# doodle_8_with_step_and_l293.net
KiCad netlist of a schematic drawn in EAGLE
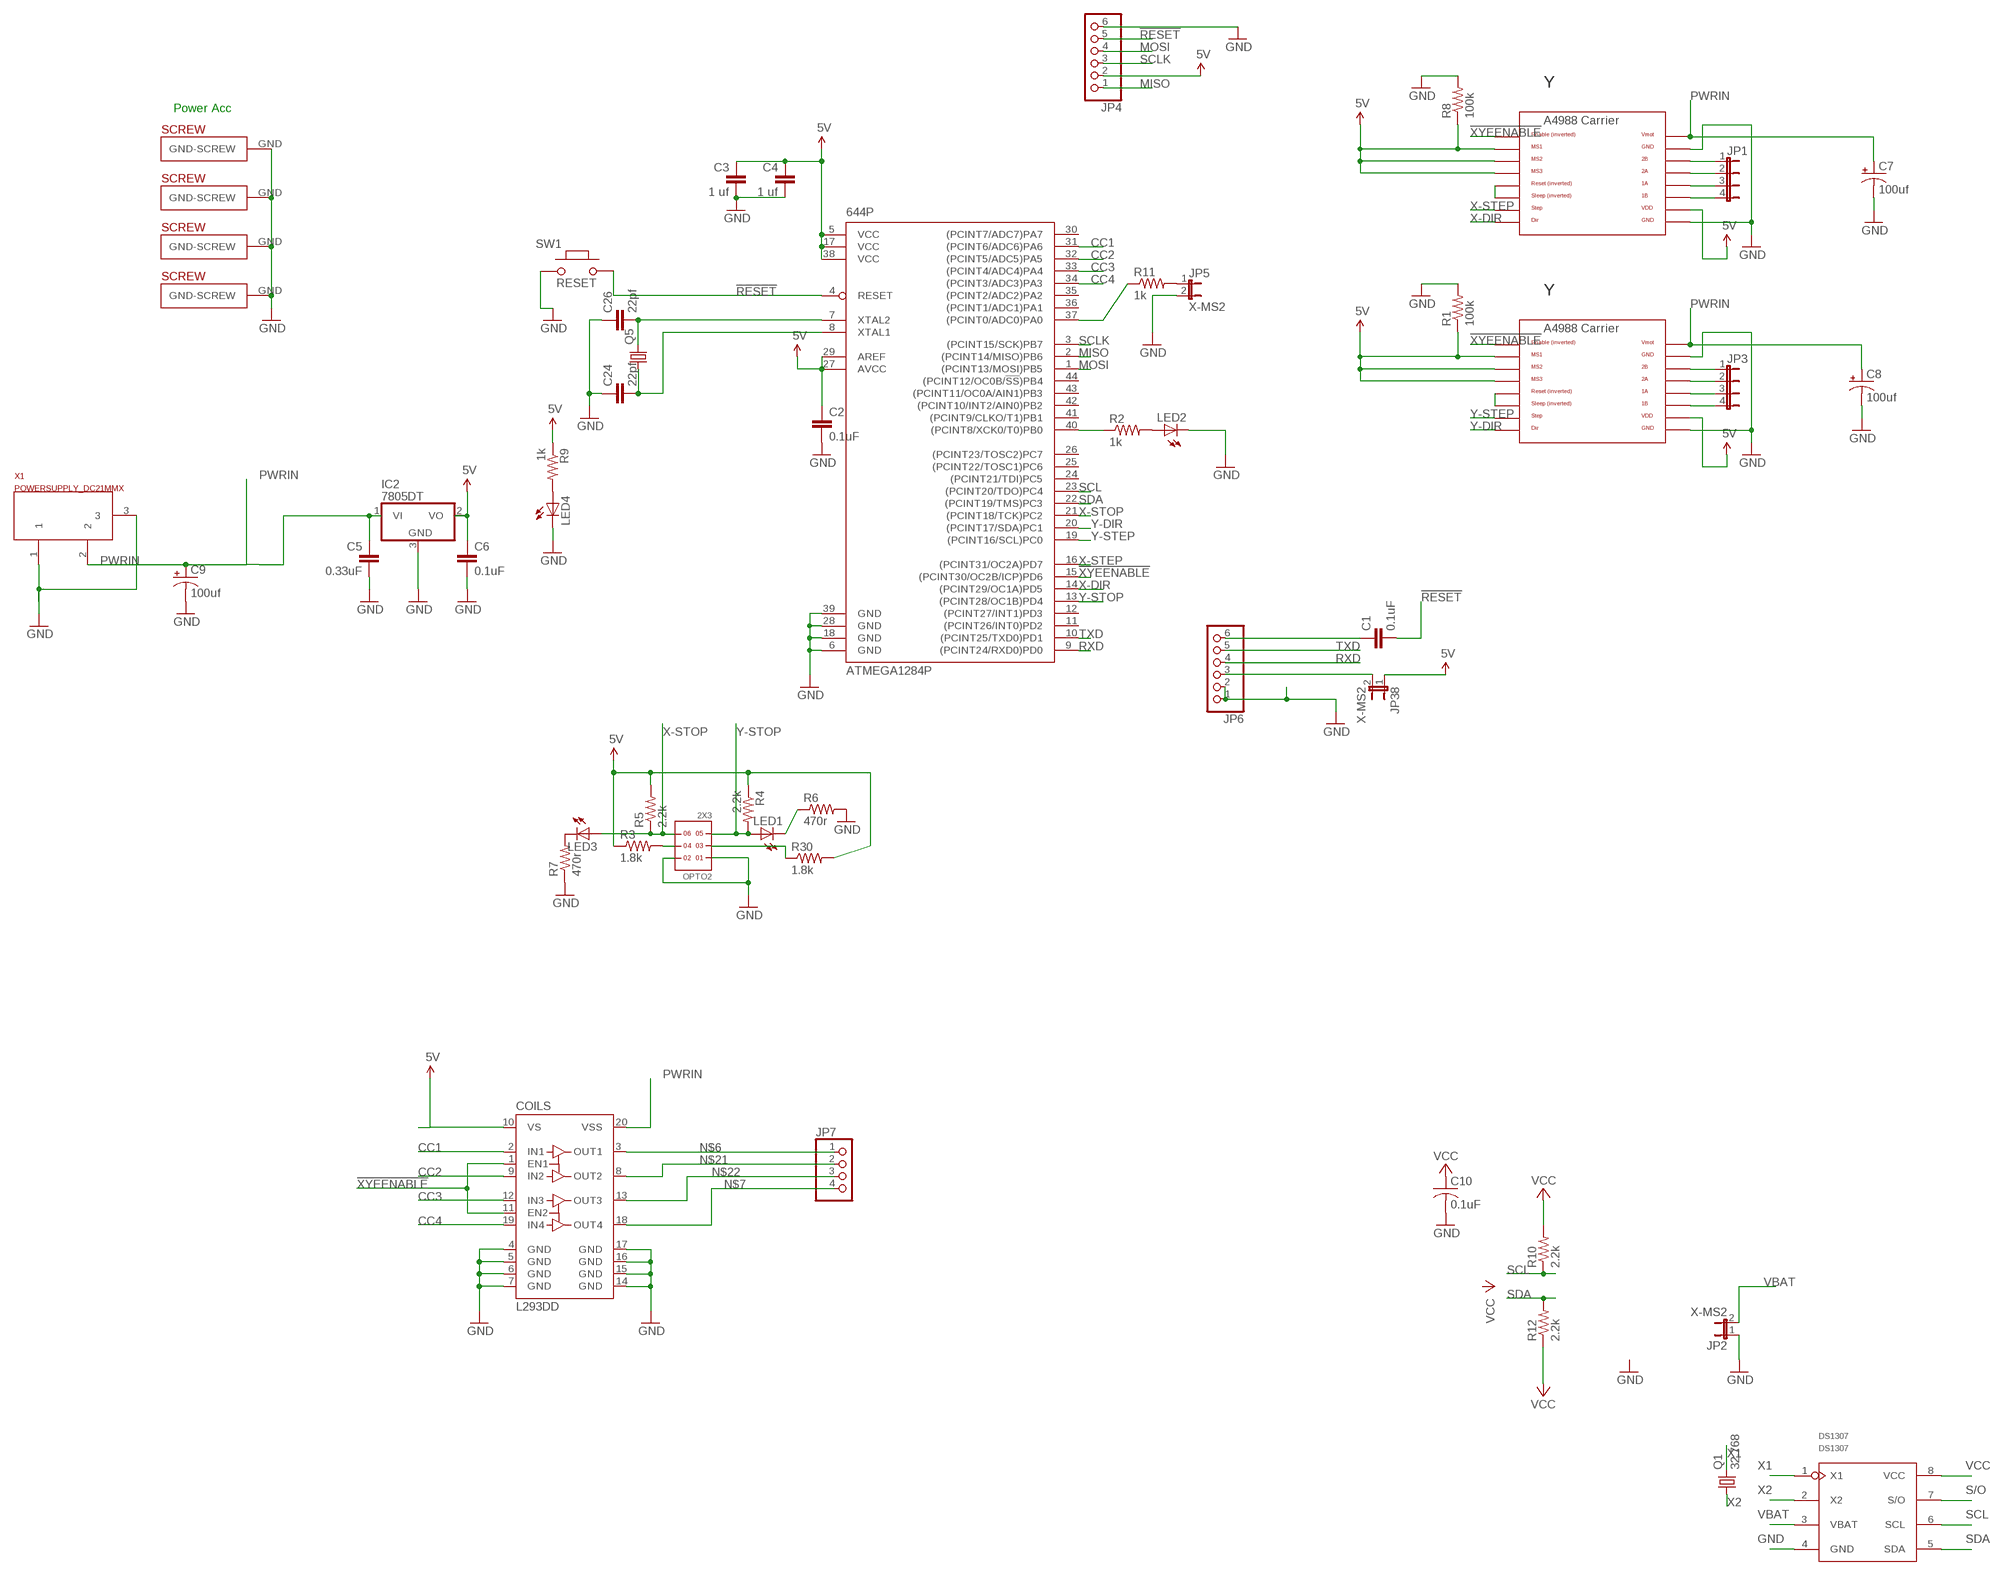
[diagram p0: schematic, sheet 1]

(export (version "E")
  (design (tool "Eeschema 10.0.6"))
  (components
    (comp (ref "644P")
      (value "ATMEGA1284P")
      (footprint "eagle-import:TQFP44")
      (fields (field (name "MPN") "ATMEGA644PV-10AU"))
      (libsource (lib "eagle-import") (part "ATMEGA644A"))
    )
    (comp (ref "C1")
      (value "0.1uF")
      (footprint "eagle-import:0805")
      (libsource (lib "eagle-import") (part "CAP0805"))
    )
    (comp (ref "C2")
      (value "0.1uF")
      (footprint "eagle-import:0805")
      (libsource (lib "eagle-import") (part "CAP0805"))
    )
    (comp (ref "C3")
      (value "1 uf")
      (footprint "eagle-import:0805")
      (libsource (lib "eagle-import") (part "CAP0805"))
    )
    (comp (ref "C4")
      (value "1 uf")
      (footprint "eagle-import:0805")
      (libsource (lib "eagle-import") (part "CAP0805"))
    )
    (comp (ref "C5")
      (value "0.33uF")
      (footprint "eagle-import:CAP-PTH-SMALL2")
      (libsource (lib "eagle-import") (part "CAPPTH2"))
    )
    (comp (ref "C6")
      (value "0.1uF")
      (footprint "eagle-import:CAP-PTH-SMALL2")
      (libsource (lib "eagle-import") (part "CAPPTH2"))
    )
    (comp (ref "C7")
      (value "100uf")
      (footprint "eagle-import:CPOL-RADIAL-100UF-25V")
      (libsource (lib "eagle-import") (part "CAP_POLPTH1"))
    )
    (comp (ref "C8")
      (value "100uf")
      (footprint "eagle-import:CPOL-RADIAL-100UF-25V")
      (libsource (lib "eagle-import") (part "CAP_POLPTH1"))
    )
    (comp (ref "C9")
      (value "100uf")
      (footprint "eagle-import:CPOL-RADIAL-100UF-25V")
      (libsource (lib "eagle-import") (part "CAP_POLPTH1"))
    )
    (comp (ref "C10")
      (value "0.1uF")
      (footprint "eagle-import:C0805")
      (libsource (lib "eagle-import") (part "C-USC0805"))
    )
    (comp (ref "C24")
      (value "22pf")
      (footprint "eagle-import:0805")
      (libsource (lib "eagle-import") (part "CAP0805"))
    )
    (comp (ref "C26")
      (value "22pf")
      (footprint "eagle-import:0805")
      (libsource (lib "eagle-import") (part "CAP0805"))
    )
    (comp (ref "COILS")
      (value "L293DD")
      (footprint "eagle-import:SO20")
      (libsource (lib "eagle-import") (part "L293DD"))
    )
    (comp (ref "DS1307")
      (value "DS1307")
      (footprint "eagle-import:SO08")
      (libsource (lib "eagle-import") (part "DS1307"))
    )
    (comp (ref "IC2")
      (value "7805DT")
      (footprint "eagle-import:TO252")
      (libsource (lib "eagle-import") (part "78DT05"))
    )
    (comp (ref "JP1")
      (value "JP4E")
      (footprint "eagle-import:JP4")
      (libsource (lib "eagle-import") (part "JP4E"))
    )
    (comp (ref "JP2")
      (value "X-MS2")
      (footprint "eagle-import:1X02")
      (libsource (lib "eagle-import") (part "JUMPER-2PTH"))
    )
    (comp (ref "JP3")
      (value "JP4E")
      (footprint "eagle-import:JP4")
      (libsource (lib "eagle-import") (part "JP4E"))
    )
    (comp (ref "JP4")
      (value "PINHD-1X6/90")
      (footprint "eagle-import:1X06_90")
      (libsource (lib "eagle-import") (part "PINHD-1X6/90"))
    )
    (comp (ref "JP5")
      (value "X-MS2")
      (footprint "eagle-import:1X02")
      (libsource (lib "eagle-import") (part "JUMPER-2PTH"))
    )
    (comp (ref "JP6")
      (value "PINHD-1X6")
      (footprint "eagle-import:1X06")
      (libsource (lib "eagle-import") (part "PINHD-1X6"))
    )
    (comp (ref "JP7")
      (value "PINHD-1X04_2.54")
      (footprint "eagle-import:1X04")
      (libsource (lib "eagle-import") (part "PINHD-1X04_2.54"))
    )
    (comp (ref "JP38")
      (value "X-MS2")
      (footprint "eagle-import:1X02")
      (libsource (lib "eagle-import") (part "JUMPER-2PTH"))
    )
    (comp (ref "LED1")
      (value "LEDCHIPLED_0805")
      (footprint "eagle-import:CHIPLED_0805")
      (libsource (lib "eagle-import") (part "LEDCHIPLED_0805"))
    )
    (comp (ref "LED2")
      (value "LEDCHIPLED_0805")
      (footprint "eagle-import:CHIPLED_0805")
      (libsource (lib "eagle-import") (part "LEDCHIPLED_0805"))
    )
    (comp (ref "LED3")
      (value "LEDCHIPLED_0805")
      (footprint "eagle-import:CHIPLED_0805")
      (libsource (lib "eagle-import") (part "LEDCHIPLED_0805"))
    )
    (comp (ref "LED4")
      (value "LEDCHIPLED_0805")
      (footprint "eagle-import:CHIPLED_0805")
      (libsource (lib "eagle-import") (part "LEDCHIPLED_0805"))
    )
    (comp (ref "OPTO2")
      (value "2X3")
      (footprint "eagle-import:2X3")
      (libsource (lib "eagle-import") (part "2X3"))
    )
    (comp (ref "Q1")
      (value "32.768")
      (footprint "eagle-import:TC38H")
      (libsource (lib "eagle-import") (part "CRYTALTC38H"))
    )
    (comp (ref "Q5")
      (value "CRYSTALHC49S")
      (footprint "eagle-import:HC49_S")
      (libsource (lib "eagle-import") (part "CRYSTALHC49S"))
    )
    (comp (ref "R1")
      (value "100k")
      (footprint "eagle-import:R0805")
      (libsource (lib "eagle-import") (part "R-US_R0805"))
    )
    (comp (ref "R2")
      (value "1k")
      (footprint "eagle-import:R0805")
      (libsource (lib "eagle-import") (part "R-US_R0805"))
    )
    (comp (ref "R3")
      (value "1.8k")
      (footprint "eagle-import:R0805")
      (libsource (lib "eagle-import") (part "R-US_R0805"))
    )
    (comp (ref "R4")
      (value "2.2k")
      (footprint "eagle-import:R0805")
      (libsource (lib "eagle-import") (part "R-US_R0805"))
    )
    (comp (ref "R5")
      (value "2.2k")
      (footprint "eagle-import:R0805")
      (libsource (lib "eagle-import") (part "R-US_R0805"))
    )
    (comp (ref "R6")
      (value "470r")
      (footprint "eagle-import:R0805")
      (libsource (lib "eagle-import") (part "R-US_R0805"))
    )
    (comp (ref "R7")
      (value "470r")
      (footprint "eagle-import:R0805")
      (libsource (lib "eagle-import") (part "R-US_R0805"))
    )
    (comp (ref "R8")
      (value "100k")
      (footprint "eagle-import:R0805")
      (libsource (lib "eagle-import") (part "R-US_R0805"))
    )
    (comp (ref "R9")
      (value "1k")
      (footprint "eagle-import:R0805")
      (libsource (lib "eagle-import") (part "R-US_R0805"))
    )
    (comp (ref "R10")
      (value "2.2k")
      (footprint "eagle-import:R0805")
      (libsource (lib "eagle-import") (part "R-US_R0805"))
    )
    (comp (ref "R11")
      (value "1k")
      (footprint "eagle-import:R0805")
      (libsource (lib "eagle-import") (part "R-US_R0805"))
    )
    (comp (ref "R12")
      (value "2.2k")
      (footprint "eagle-import:R0805")
      (libsource (lib "eagle-import") (part "R-US_R0805"))
    )
    (comp (ref "R30")
      (value "1.8k")
      (footprint "eagle-import:R0603")
      (libsource (lib "eagle-import") (part "R-US_R0603"))
    )
    (comp (ref "SW1")
      (value "RESET")
      (footprint "eagle-import:157SW")
      (libsource (lib "eagle-import") (part "PB157"))
    )
    (comp (ref "U$1")
      (value "A4988BREAKOUT")
      (footprint "eagle-import:A4988BREAKOUT")
      (libsource (lib "eagle-import") (part "A4988BREAKOUT"))
    )
    (comp (ref "U$7")
      (value "A4988BREAKOUT")
      (footprint "eagle-import:A4988BREAKOUT")
      (libsource (lib "eagle-import") (part "A4988BREAKOUT"))
    )
    (comp (ref "U$14")
      (value "PLATED-SCREW")
      (footprint "eagle-import:PLATEDSCREW")
      (libsource (lib "eagle-import") (part "PLATED-SCREW"))
    )
    (comp (ref "U$17")
      (value "PLATED-SCREW")
      (footprint "eagle-import:PLATEDSCREW")
      (libsource (lib "eagle-import") (part "PLATED-SCREW"))
    )
    (comp (ref "U$18")
      (value "PLATED-SCREW")
      (footprint "eagle-import:PLATEDSCREW")
      (libsource (lib "eagle-import") (part "PLATED-SCREW"))
    )
    (comp (ref "U$38")
      (value "PLATED-SCREW")
      (footprint "eagle-import:PLATEDSCREW")
      (libsource (lib "eagle-import") (part "PLATED-SCREW"))
    )
    (comp (ref "X1")
      (value "POWERSUPPLY_DC21MMX")
      (footprint "eagle-import:POWERSUPPLY_DC-21MM")
      (libsource (lib "eagle-import") (part "POWERSUPPLY_DC21MMX"))
    )
  )
  (nets
    (net (code "1") (name "/CC1") (class "Default")
      (node (ref "644P") (pin "31") (pinfunction "(PCINT6/ADC6)PA6_31") (pintype "bidirectional"))
      (node (ref "COILS") (pin "2") (pinfunction "IN1_2") (pintype "input"))
    )
    (net (code "2") (name "/CC2") (class "Default")
      (node (ref "644P") (pin "32") (pinfunction "(PCINT5/ADC5)PA5_32") (pintype "bidirectional"))
      (node (ref "COILS") (pin "9") (pinfunction "IN2_9") (pintype "input"))
    )
    (net (code "3") (name "/CC3") (class "Default")
      (node (ref "644P") (pin "33") (pinfunction "(PCINT4/ADC4)PA4_33") (pintype "bidirectional"))
      (node (ref "COILS") (pin "12") (pinfunction "IN3_12") (pintype "input"))
    )
    (net (code "4") (name "/CC4") (class "Default")
      (node (ref "644P") (pin "34") (pinfunction "(PCINT3/ADC3)PA3_34") (pintype "bidirectional"))
      (node (ref "COILS") (pin "19") (pinfunction "IN4_19") (pintype "input"))
    )
    (net (code "5") (name "/MISO") (class "Default")
      (node (ref "644P") (pin "2") (pinfunction "(PCINT14/MISO)PB6_2") (pintype "bidirectional"))
      (node (ref "JP4") (pin "1") (pinfunction "1_1") (pintype "passive"))
    )
    (net (code "6") (name "/MOSI") (class "Default")
      (node (ref "644P") (pin "1") (pinfunction "(PCINT13/MOSI)PB5_1") (pintype "bidirectional"))
      (node (ref "JP4") (pin "4") (pinfunction "4_4") (pintype "passive"))
    )
    (net (code "7") (name "/N$6") (class "Default")
      (node (ref "COILS") (pin "3") (pinfunction "OUT1_3") (pintype "output"))
      (node (ref "JP7") (pin "1") (pinfunction "1_1") (pintype "passive"))
    )
    (net (code "8") (name "/N$7") (class "Default")
      (node (ref "COILS") (pin "18") (pinfunction "OUT4_18") (pintype "output"))
      (node (ref "JP7") (pin "4") (pinfunction "4_4") (pintype "passive"))
    )
    (net (code "9") (name "/N$21") (class "Default")
      (node (ref "COILS") (pin "8") (pinfunction "OUT2_8") (pintype "output"))
      (node (ref "JP7") (pin "2") (pinfunction "2_2") (pintype "passive"))
    )
    (net (code "10") (name "/N$22") (class "Default")
      (node (ref "COILS") (pin "13") (pinfunction "OUT3_13") (pintype "output"))
      (node (ref "JP7") (pin "3") (pinfunction "3_3") (pintype "passive"))
    )
    (net (code "11") (name "/PWRIN") (class "Default")
      (node (ref "C5") (pin "1") (pinfunction "1_1") (pintype "passive"))
      (node (ref "C7") (pin "1") (pinfunction "+_1") (pintype "passive"))
      (node (ref "C8") (pin "1") (pinfunction "+_1") (pintype "passive"))
      (node (ref "C9") (pin "1") (pinfunction "+_1") (pintype "passive"))
      (node (ref "COILS") (pin "20") (pinfunction "VSS_20") (pintype "power_in"))
      (node (ref "IC2") (pin "1") (pinfunction "VI_1") (pintype "input"))
      (node (ref "U$1") (pin "VMOT") (pinfunction "VMOT_VMOT") (pintype "power_in"))
      (node (ref "U$7") (pin "VMOT") (pinfunction "VMOT_VMOT") (pintype "power_in"))
      (node (ref "X1") (pin "2") (pinfunction "2_2") (pintype "power_in"))
    )
    (net (code "12") (name "/RXD") (class "Default")
      (node (ref "644P") (pin "9") (pinfunction "(PCINT24/RXD0)PD0_9") (pintype "bidirectional"))
      (node (ref "JP6") (pin "4") (pinfunction "4_4") (pintype "passive"))
    )
    (net (code "13") (name "/SCL") (class "Default")
      (node (ref "644P") (pin "23") (pinfunction "(PCINT20/TDO)PC4_23") (pintype "output"))
      (node (ref "DS1307") (pin "6") (pinfunction "SCL_6") (pintype "bidirectional"))
      (node (ref "R10") (pin "1") (pinfunction "1_1") (pintype "passive"))
    )
    (net (code "14") (name "/SCLK") (class "Default")
      (node (ref "644P") (pin "3") (pinfunction "(PCINT15/SCK)PB7_3") (pintype "bidirectional"))
      (node (ref "JP4") (pin "3") (pinfunction "3_3") (pintype "passive"))
    )
    (net (code "15") (name "/SDA") (class "Default")
      (node (ref "644P") (pin "22") (pinfunction "(PCINT19/TMS)PC3_22") (pintype "output"))
      (node (ref "DS1307") (pin "5") (pinfunction "SDA_5") (pintype "bidirectional"))
      (node (ref "R12") (pin "2") (pinfunction "2_2") (pintype "passive"))
    )
    (net (code "16") (name "/S{slash}O") (class "Default")
      (node (ref "DS1307") (pin "7") (pinfunction "S/O_7") (pintype "bidirectional"))
    )
    (net (code "17") (name "/TXD") (class "Default")
      (node (ref "644P") (pin "10") (pinfunction "(PCINT25/TXD0)PD1_10") (pintype "bidirectional"))
      (node (ref "JP6") (pin "5") (pinfunction "5_5") (pintype "passive"))
    )
    (net (code "18") (name "/VBAT") (class "Default")
      (node (ref "DS1307") (pin "3") (pinfunction "VBAT_3") (pintype "bidirectional"))
      (node (ref "JP2") (pin "2") (pinfunction "2_2") (pintype "passive"))
    )
    (net (code "19") (name "/X-DIR") (class "Default")
      (node (ref "644P") (pin "14") (pinfunction "(PCINT29/OC1A)PD5_14") (pintype "bidirectional"))
      (node (ref "U$7") (pin "DIR") (pinfunction "DIR_DIR") (pintype "input"))
    )
    (net (code "20") (name "/X-STEP") (class "Default")
      (node (ref "644P") (pin "16") (pinfunction "(PCINT31/OC2A)PD7_16") (pintype "bidirectional"))
      (node (ref "U$7") (pin "STEP") (pinfunction "STEP_STEP") (pintype "input"))
    )
    (net (code "21") (name "/X-STOP") (class "Default")
      (node (ref "644P") (pin "21") (pinfunction "(PCINT18/TCK)PC2_21") (pintype "output"))
      (node (ref "LED3") (pin "A") (pinfunction "A_A") (pintype "passive"))
      (node (ref "OPTO2") (pin "6") (pinfunction "6_6") (pintype "bidirectional"))
      (node (ref "R5") (pin "1") (pinfunction "1_1") (pintype "passive"))
    )
    (net (code "22") (name "/X1") (class "Default")
      (node (ref "DS1307") (pin "1") (pinfunction "X1_1") (pintype "bidirectional"))
      (node (ref "Q1") (pin "2") (pinfunction "2_2") (pintype "passive"))
    )
    (net (code "23") (name "/X2") (class "Default")
      (node (ref "DS1307") (pin "2") (pinfunction "X2_2") (pintype "bidirectional"))
      (node (ref "Q1") (pin "1") (pinfunction "1_1") (pintype "passive"))
    )
    (net (code "24") (name "/Y-DIR") (class "Default")
      (node (ref "644P") (pin "20") (pinfunction "(PCINT17/SDA)PC1_20") (pintype "output"))
      (node (ref "U$1") (pin "DIR") (pinfunction "DIR_DIR") (pintype "input"))
    )
    (net (code "25") (name "/Y-STEP") (class "Default")
      (node (ref "644P") (pin "19") (pinfunction "(PCINT16/SCL)PC0_19") (pintype "output"))
      (node (ref "U$1") (pin "STEP") (pinfunction "STEP_STEP") (pintype "input"))
    )
    (net (code "26") (name "/Y-STOP") (class "Default")
      (node (ref "644P") (pin "13") (pinfunction "(PCINT28/OC1B)PD4_13") (pintype "bidirectional"))
      (node (ref "LED1") (pin "A") (pinfunction "A_A") (pintype "passive"))
      (node (ref "OPTO2") (pin "5") (pinfunction "5_5") (pintype "bidirectional"))
      (node (ref "R4") (pin "2") (pinfunction "2_2") (pintype "passive"))
    )
    (net (code "27") (name "/~{RESET}") (class "Default")
      (node (ref "644P") (pin "4") (pinfunction "RESET_4") (pintype "input"))
      (node (ref "C1") (pin "2") (pinfunction "2_2") (pintype "passive"))
      (node (ref "JP4") (pin "5") (pinfunction "5_5") (pintype "passive"))
      (node (ref "SW1") (pin "2") (pinfunction "2_2") (pintype "passive"))
    )
    (net (code "28") (name "/~{XYEENABLE}") (class "Default")
      (node (ref "644P") (pin "15") (pinfunction "(PCINT30/OC2B/ICP)PD6_15") (pintype "bidirectional"))
      (node (ref "COILS") (pin "1") (pinfunction "EN1_1") (pintype "input"))
      (node (ref "COILS") (pin "11") (pinfunction "EN2_11") (pintype "input"))
      (node (ref "U$1") (pin "EN") (pinfunction "EN_EN") (pintype "input"))
      (node (ref "U$7") (pin "EN") (pinfunction "EN_EN") (pintype "input"))
    )
    (net (code "29") (name "5V") (class "Default")
      (node (ref "644P") (pin "17") (pinfunction "VCC_17") (pintype "power_in"))
      (node (ref "644P") (pin "27") (pinfunction "AVCC_27") (pintype "power_in"))
      (node (ref "644P") (pin "29") (pinfunction "AREF_29") (pintype "passive"))
      (node (ref "644P") (pin "38") (pinfunction "VCC_38") (pintype "power_in"))
      (node (ref "644P") (pin "5") (pinfunction "VCC_5") (pintype "power_in"))
      (node (ref "C2") (pin "1") (pinfunction "1_1") (pintype "passive"))
      (node (ref "C3") (pin "1") (pinfunction "1_1") (pintype "passive"))
      (node (ref "C4") (pin "1") (pinfunction "1_1") (pintype "passive"))
      (node (ref "C6") (pin "1") (pinfunction "1_1") (pintype "passive"))
      (node (ref "COILS") (pin "10") (pinfunction "VS_10") (pintype "power_in"))
      (node (ref "IC2") (pin "2") (pinfunction "VO_2") (pintype "passive"))
      (node (ref "JP38") (pin "1") (pinfunction "1_1") (pintype "passive"))
      (node (ref "JP4") (pin "2") (pinfunction "2_2") (pintype "passive"))
      (node (ref "R1") (pin "1") (pinfunction "1_1") (pintype "passive"))
      (node (ref "R3") (pin "1") (pinfunction "1_1") (pintype "passive"))
      (node (ref "R30") (pin "2") (pinfunction "2_2") (pintype "passive"))
      (node (ref "R4") (pin "1") (pinfunction "1_1") (pintype "passive"))
      (node (ref "R5") (pin "2") (pinfunction "2_2") (pintype "passive"))
      (node (ref "R8") (pin "1") (pinfunction "1_1") (pintype "passive"))
      (node (ref "R9") (pin "1") (pinfunction "1_1") (pintype "passive"))
      (node (ref "U$1") (pin "MS1") (pinfunction "MS1_MS1") (pintype "input"))
      (node (ref "U$1") (pin "MS2") (pinfunction "MS2_MS2") (pintype "input"))
      (node (ref "U$1") (pin "MS3") (pinfunction "MS3_MS3") (pintype "input"))
      (node (ref "U$1") (pin "VDD") (pinfunction "VDD_VDD") (pintype "power_in"))
      (node (ref "U$7") (pin "MS1") (pinfunction "MS1_MS1") (pintype "input"))
      (node (ref "U$7") (pin "MS2") (pinfunction "MS2_MS2") (pintype "input"))
      (node (ref "U$7") (pin "MS3") (pinfunction "MS3_MS3") (pintype "input"))
      (node (ref "U$7") (pin "VDD") (pinfunction "VDD_VDD") (pintype "power_in"))
    )
    (net (code "30") (name "GND") (class "Default")
      (node (ref "644P") (pin "18") (pinfunction "GND_18") (pintype "power_in"))
      (node (ref "644P") (pin "28") (pinfunction "GND_28") (pintype "power_in"))
      (node (ref "644P") (pin "39") (pinfunction "GND_39") (pintype "power_in"))
      (node (ref "644P") (pin "6") (pinfunction "GND_6") (pintype "power_in"))
      (node (ref "C10") (pin "2") (pinfunction "2_2") (pintype "passive"))
      (node (ref "C2") (pin "2") (pinfunction "2_2") (pintype "passive"))
      (node (ref "C24") (pin "1") (pinfunction "1_1") (pintype "passive"))
      (node (ref "C26") (pin "1") (pinfunction "1_1") (pintype "passive"))
      (node (ref "C3") (pin "2") (pinfunction "2_2") (pintype "passive"))
      (node (ref "C4") (pin "2") (pinfunction "2_2") (pintype "passive"))
      (node (ref "C5") (pin "2") (pinfunction "2_2") (pintype "passive"))
      (node (ref "C6") (pin "2") (pinfunction "2_2") (pintype "passive"))
      (node (ref "C7") (pin "2") (pinfunction "-_2") (pintype "passive"))
      (node (ref "C8") (pin "2") (pinfunction "-_2") (pintype "passive"))
      (node (ref "C9") (pin "2") (pinfunction "-_2") (pintype "passive"))
      (node (ref "COILS") (pin "14") (pinfunction "GND_14") (pintype "power_in"))
      (node (ref "COILS") (pin "15") (pinfunction "GND_15") (pintype "power_in"))
      (node (ref "COILS") (pin "16") (pinfunction "GND_16") (pintype "power_in"))
      (node (ref "COILS") (pin "17") (pinfunction "GND_17") (pintype "power_in"))
      (node (ref "COILS") (pin "4") (pinfunction "GND_4") (pintype "power_in"))
      (node (ref "COILS") (pin "5") (pinfunction "GND_5") (pintype "power_in"))
      (node (ref "COILS") (pin "6") (pinfunction "GND_6") (pintype "power_in"))
      (node (ref "COILS") (pin "7") (pinfunction "GND_7") (pintype "power_in"))
      (node (ref "DS1307") (pin "4") (pinfunction "GND_4") (pintype "bidirectional"))
      (node (ref "IC2") (pin "3") (pinfunction "GND_3") (pintype "passive"))
      (node (ref "JP2") (pin "1") (pinfunction "1_1") (pintype "passive"))
      (node (ref "JP4") (pin "6") (pinfunction "6_6") (pintype "passive"))
      (node (ref "JP5") (pin "2") (pinfunction "2_2") (pintype "passive"))
      (node (ref "JP6") (pin "1") (pinfunction "1_1") (pintype "passive"))
      (node (ref "JP6") (pin "2") (pinfunction "2_2") (pintype "passive"))
      (node (ref "LED2") (pin "C") (pinfunction "C_C") (pintype "passive"))
      (node (ref "LED4") (pin "C") (pinfunction "C_C") (pintype "passive"))
      (node (ref "OPTO2") (pin "1") (pinfunction "1_1") (pintype "bidirectional"))
      (node (ref "OPTO2") (pin "2") (pinfunction "2_2") (pintype "bidirectional"))
      (node (ref "R1") (pin "2") (pinfunction "2_2") (pintype "passive"))
      (node (ref "R6") (pin "2") (pinfunction "2_2") (pintype "passive"))
      (node (ref "R7") (pin "1") (pinfunction "1_1") (pintype "passive"))
      (node (ref "R8") (pin "2") (pinfunction "2_2") (pintype "passive"))
      (node (ref "SW1") (pin "1") (pinfunction "1_1") (pintype "passive"))
      (node (ref "U$1") (pin "GND") (pinfunction "GND_GND") (pintype "power_in"))
      (node (ref "U$1") (pin "GND@0") (pinfunction "GND_GND@0") (pintype "power_in"))
      (node (ref "U$14") (pin "GND") (pinfunction "GND-SCREW_GND") (pintype "bidirectional"))
      (node (ref "U$17") (pin "GND") (pinfunction "GND-SCREW_GND") (pintype "bidirectional"))
      (node (ref "U$18") (pin "GND") (pinfunction "GND-SCREW_GND") (pintype "bidirectional"))
      (node (ref "U$38") (pin "GND") (pinfunction "GND-SCREW_GND") (pintype "bidirectional"))
      (node (ref "U$7") (pin "GND") (pinfunction "GND_GND") (pintype "power_in"))
      (node (ref "U$7") (pin "GND@0") (pinfunction "GND_GND@0") (pintype "power_in"))
      (node (ref "X1") (pin "1") (pinfunction "1_1") (pintype "power_in"))
      (node (ref "X1") (pin "3") (pinfunction "3_3") (pintype "power_in"))
    )
    (net (code "31") (name "Net-(644P-(PCINT0{slash}ADC0)PA0)") (class "Default")
      (node (ref "644P") (pin "37") (pinfunction "(PCINT0/ADC0)PA0_37") (pintype "bidirectional"))
      (node (ref "R11") (pin "1") (pinfunction "1_1") (pintype "passive"))
    )
    (net (code "32") (name "Net-(644P-(PCINT8{slash}XCK0{slash}T0)PB0)") (class "Default")
      (node (ref "644P") (pin "40") (pinfunction "(PCINT8/XCK0/T0)PB0_40") (pintype "bidirectional"))
      (node (ref "R2") (pin "1") (pinfunction "1_1") (pintype "passive"))
    )
    (net (code "33") (name "Net-(644P-XTAL1)") (class "Default")
      (node (ref "644P") (pin "8") (pinfunction "XTAL1_8") (pintype "bidirectional"))
      (node (ref "C24") (pin "2") (pinfunction "2_2") (pintype "passive"))
      (node (ref "Q5") (pin "1") (pinfunction "1_1") (pintype "passive"))
    )
    (net (code "34") (name "Net-(644P-XTAL2)") (class "Default")
      (node (ref "644P") (pin "7") (pinfunction "XTAL2_7") (pintype "bidirectional"))
      (node (ref "C26") (pin "2") (pinfunction "2_2") (pintype "passive"))
      (node (ref "Q5") (pin "2") (pinfunction "2_2") (pintype "passive"))
    )
    (net (code "35") (name "Net-(C1-Pad1)") (class "Default")
      (node (ref "C1") (pin "1") (pinfunction "1_1") (pintype "passive"))
      (node (ref "JP6") (pin "6") (pinfunction "6_6") (pintype "passive"))
    )
    (net (code "36") (name "Net-(JP1-Pad1)") (class "Default")
      (node (ref "JP1") (pin "1") (pinfunction "1_1") (pintype "passive"))
      (node (ref "U$7") (pin "2B") (pinfunction "2B_2B") (pintype "output"))
    )
    (net (code "37") (name "Net-(JP1-Pad2)") (class "Default")
      (node (ref "JP1") (pin "2") (pinfunction "2_2") (pintype "passive"))
      (node (ref "U$7") (pin "2A") (pinfunction "2A_2A") (pintype "output"))
    )
    (net (code "38") (name "Net-(JP1-Pad3)") (class "Default")
      (node (ref "JP1") (pin "3") (pinfunction "3_3") (pintype "passive"))
      (node (ref "U$7") (pin "1A") (pinfunction "1A_1A") (pintype "output"))
    )
    (net (code "39") (name "Net-(JP1-Pad4)") (class "Default")
      (node (ref "JP1") (pin "4") (pinfunction "4_4") (pintype "passive"))
      (node (ref "U$7") (pin "1B") (pinfunction "1B_1B") (pintype "output"))
    )
    (net (code "40") (name "Net-(JP3-Pad1)") (class "Default")
      (node (ref "JP3") (pin "1") (pinfunction "1_1") (pintype "passive"))
      (node (ref "U$1") (pin "2B") (pinfunction "2B_2B") (pintype "output"))
    )
    (net (code "41") (name "Net-(JP3-Pad2)") (class "Default")
      (node (ref "JP3") (pin "2") (pinfunction "2_2") (pintype "passive"))
      (node (ref "U$1") (pin "2A") (pinfunction "2A_2A") (pintype "output"))
    )
    (net (code "42") (name "Net-(JP3-Pad3)") (class "Default")
      (node (ref "JP3") (pin "3") (pinfunction "3_3") (pintype "passive"))
      (node (ref "U$1") (pin "1A") (pinfunction "1A_1A") (pintype "output"))
    )
    (net (code "43") (name "Net-(JP3-Pad4)") (class "Default")
      (node (ref "JP3") (pin "4") (pinfunction "4_4") (pintype "passive"))
      (node (ref "U$1") (pin "1B") (pinfunction "1B_1B") (pintype "output"))
    )
    (net (code "44") (name "Net-(JP5-Pad1)") (class "Default")
      (node (ref "JP5") (pin "1") (pinfunction "1_1") (pintype "passive"))
      (node (ref "R11") (pin "2") (pinfunction "2_2") (pintype "passive"))
    )
    (net (code "45") (name "Net-(JP38-Pad2)") (class "Default")
      (node (ref "JP38") (pin "2") (pinfunction "2_2") (pintype "passive"))
      (node (ref "JP6") (pin "3") (pinfunction "3_3") (pintype "passive"))
    )
    (net (code "46") (name "Net-(LED1-PadC)") (class "Default")
      (node (ref "LED1") (pin "C") (pinfunction "C_C") (pintype "passive"))
      (node (ref "R6") (pin "1") (pinfunction "1_1") (pintype "passive"))
    )
    (net (code "47") (name "Net-(LED2-PadA)") (class "Default")
      (node (ref "LED2") (pin "A") (pinfunction "A_A") (pintype "passive"))
      (node (ref "R2") (pin "2") (pinfunction "2_2") (pintype "passive"))
    )
    (net (code "48") (name "Net-(LED3-PadC)") (class "Default")
      (node (ref "LED3") (pin "C") (pinfunction "C_C") (pintype "passive"))
      (node (ref "R7") (pin "2") (pinfunction "2_2") (pintype "passive"))
    )
    (net (code "49") (name "Net-(LED4-PadA)") (class "Default")
      (node (ref "LED4") (pin "A") (pinfunction "A_A") (pintype "passive"))
      (node (ref "R9") (pin "2") (pinfunction "2_2") (pintype "passive"))
    )
    (net (code "50") (name "Net-(OPTO2-Pad3)") (class "Default")
      (node (ref "OPTO2") (pin "3") (pinfunction "3_3") (pintype "bidirectional"))
      (node (ref "R30") (pin "1") (pinfunction "1_1") (pintype "passive"))
    )
    (net (code "51") (name "Net-(OPTO2-Pad4)") (class "Default")
      (node (ref "OPTO2") (pin "4") (pinfunction "4_4") (pintype "bidirectional"))
      (node (ref "R3") (pin "2") (pinfunction "2_2") (pintype "passive"))
    )
    (net (code "52") (name "Net-(U$1-SLEEP)") (class "Default")
      (node (ref "U$1") (pin "RST") (pinfunction "RST_RST") (pintype "input"))
      (node (ref "U$1") (pin "SLP") (pinfunction "SLEEP_SLP") (pintype "input"))
    )
    (net (code "53") (name "Net-(U$7-SLEEP)") (class "Default")
      (node (ref "U$7") (pin "RST") (pinfunction "RST_RST") (pintype "input"))
      (node (ref "U$7") (pin "SLP") (pinfunction "SLEEP_SLP") (pintype "input"))
    )
    (net (code "54") (name "VCC") (class "Default")
      (node (ref "C10") (pin "1") (pinfunction "1_1") (pintype "passive"))
      (node (ref "DS1307") (pin "8") (pinfunction "VCC_8") (pintype "bidirectional"))
      (node (ref "R10") (pin "2") (pinfunction "2_2") (pintype "passive"))
      (node (ref "R12") (pin "1") (pinfunction "1_1") (pintype "passive"))
    )
    (net (code "55") (name "unconnected-(644P-(PCINT1{slash}ADC1)PA1-Pad36)") (class "Default")
      (node (ref "644P") (pin "36") (pinfunction "(PCINT1/ADC1)PA1_36") (pintype "bidirectional"))
    )
    (net (code "56") (name "unconnected-(644P-(PCINT2{slash}ADC2)PA2-Pad35)") (class "Default")
      (node (ref "644P") (pin "35") (pinfunction "(PCINT2/ADC2)PA2_35") (pintype "bidirectional"))
    )
    (net (code "57") (name "unconnected-(644P-(PCINT7{slash}ADC7)PA7-Pad30)") (class "Default")
      (node (ref "644P") (pin "30") (pinfunction "(PCINT7/ADC7)PA7_30") (pintype "bidirectional"))
    )
    (net (code "58") (name "unconnected-(644P-(PCINT9{slash}CLKO{slash}T1)PB1-Pad41)") (class "Default")
      (node (ref "644P") (pin "41") (pinfunction "(PCINT9/CLKO/T1)PB1_41") (pintype "bidirectional"))
    )
    (net (code "59") (name "unconnected-(644P-(PCINT10{slash}INT2{slash}AIN0)PB2-Pad42)") (class "Default")
      (node (ref "644P") (pin "42") (pinfunction "(PCINT10/INT2/AIN0)PB2_42") (pintype "bidirectional"))
    )
    (net (code "60") (name "unconnected-(644P-(PCINT11{slash}OC0A{slash}AIN1)PB3-Pad43)") (class "Default")
      (node (ref "644P") (pin "43") (pinfunction "(PCINT11/OC0A/AIN1)PB3_43") (pintype "bidirectional"))
    )
    (net (code "61") (name "unconnected-(644P-(PCINT12{slash}OC0B{slash}~{SS})PB4-Pad44)") (class "Default")
      (node (ref "644P") (pin "44") (pinfunction "(PCINT12/OC0B/~{SS})PB4_44") (pintype "bidirectional"))
    )
    (net (code "62") (name "unconnected-(644P-(PCINT21{slash}TDI)PC5-Pad24)") (class "Default")
      (node (ref "644P") (pin "24") (pinfunction "(PCINT21/TDI)PC5_24") (pintype "output"))
    )
    (net (code "63") (name "unconnected-(644P-(PCINT22{slash}TOSC1)PC6-Pad25)") (class "Default")
      (node (ref "644P") (pin "25") (pinfunction "(PCINT22/TOSC1)PC6_25") (pintype "output"))
    )
    (net (code "64") (name "unconnected-(644P-(PCINT23{slash}TOSC2)PC7-Pad26)") (class "Default")
      (node (ref "644P") (pin "26") (pinfunction "(PCINT23/TOSC2)PC7_26") (pintype "output"))
    )
    (net (code "65") (name "unconnected-(644P-(PCINT26{slash}INT0)PD2-Pad11)") (class "Default")
      (node (ref "644P") (pin "11") (pinfunction "(PCINT26/INT0)PD2_11") (pintype "bidirectional"))
    )
    (net (code "66") (name "unconnected-(644P-(PCINT27{slash}INT1)PD3-Pad12)") (class "Default")
      (node (ref "644P") (pin "12") (pinfunction "(PCINT27/INT1)PD3_12") (pintype "bidirectional"))
    )
  )
)
